# ST_LINK_V2-1.net
KiCad netlist of a schematic drawn in Altium Designer
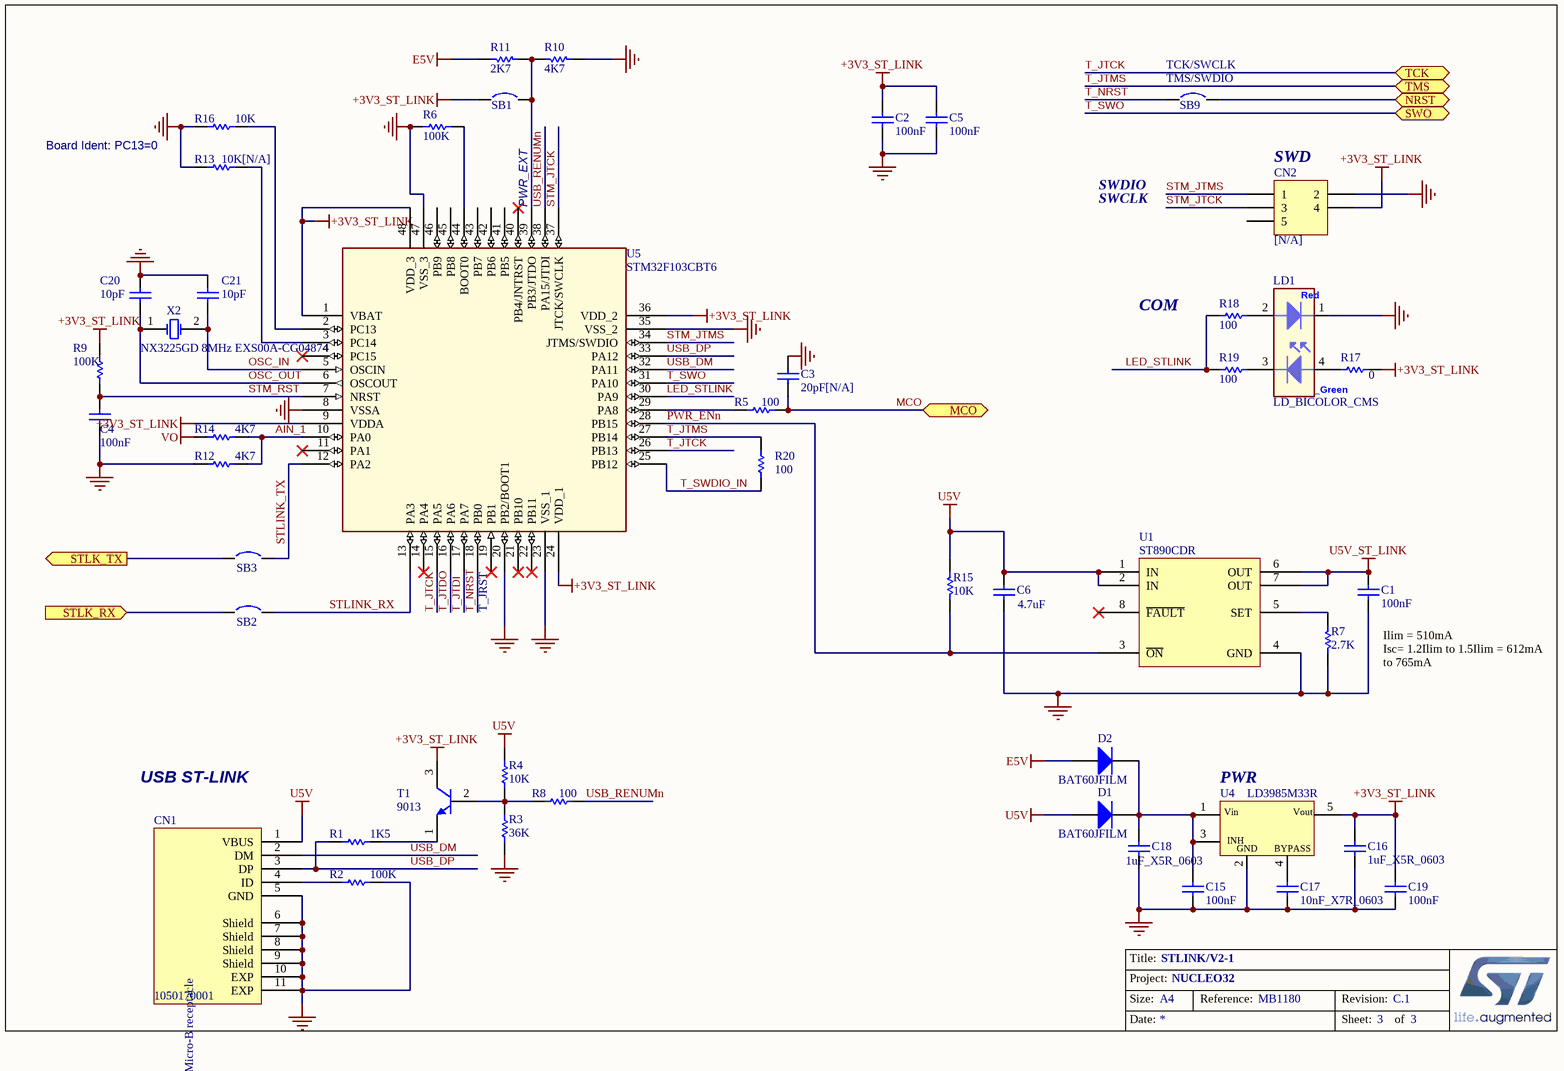
[diagram p0: ST_LINK_V2-1.SCHDOC]

(export (version "E")
  (design (tool "Eeschema 10.0.6"))
  (components
    (comp (ref "C1")
      (value "100nF")
      (footprint "0603C")
      (description "Capacitor 0402 / 0603 / 0805")
      (libsource (lib "MCD_TOOLS") (part "Capacitor_ST"))
    )
    (comp (ref "C2")
      (value "100nF")
      (footprint "0603C")
      (description "Capacitor 0402 / 0603 / 0805")
      (libsource (lib "MCD_TOOLS") (part "Capacitor_ST"))
    )
    (comp (ref "C3")
      (value "20pF[N/A]")
      (footprint "0603C")
      (description "Capacitor 0402 / 0603 / 0805")
      (libsource (lib "MCD_TOOLS") (part "Capacitor_ST"))
    )
    (comp (ref "C4")
      (value "100nF")
      (footprint "0603C")
      (description "Capacitor 0402 / 0603 / 0805")
      (libsource (lib "MCD_TOOLS") (part "Capacitor_ST"))
    )
    (comp (ref "C5")
      (value "100nF")
      (footprint "0603C")
      (description "Capacitor 0402 / 0603 / 0805")
      (libsource (lib "MCD_TOOLS") (part "Capacitor_ST"))
    )
    (comp (ref "C6")
      (value "4.7uF")
      (footprint "0603C")
      (description "0603  X5R 1µF")
      (fields (field (name "TOLERANCE") "10%"))
      (libsource (lib "MB963_1") (part "CAP SMD 0603  X5R 1µF 25V 10%"))
    )
    (comp (ref "C15")
      (value "100nF")
      (footprint "0603C")
      (description "Capacitor 0402 / 0603 / 0805")
      (libsource (lib "MCD_TOOLS") (part "Capacitor_ST"))
    )
    (comp (ref "C16")
      (value "1uF_X5R_0603")
      (footprint "0603C")
      (description "0603  X5R 1µF")
      (fields (field (name "TOLERANCE") "10%"))
      (libsource (lib "MB963_1") (part "CAP SMD 0603  X5R 1µF 25V 10%"))
    )
    (comp (ref "C17")
      (value "10nF_X7R_0603")
      (footprint "0603C")
      (description "0603  X7R 10NF")
      (fields (field (name "TOLERANCE") "10%"))
      (libsource (lib "MB963_1") (part "CAP SMD 0603  X7R 10000PF 50V 10%"))
    )
    (comp (ref "C18")
      (value "1uF_X5R_0603")
      (footprint "0603C")
      (description "0603  X5R 1µF")
      (fields (field (name "TOLERANCE") "10%"))
      (libsource (lib "MB963_1") (part "CAP SMD 0603  X5R 1µF 25V 10%"))
    )
    (comp (ref "C19")
      (value "100nF")
      (footprint "0603C")
      (description "Capacitor 0402 / 0603 / 0805")
      (libsource (lib "MCD_TOOLS") (part "Capacitor_ST"))
    )
    (comp (ref "C20")
      (value "10pF")
      (footprint "0603C")
      (description "Capacitor 0402 / 0603 / 0805")
      (libsource (lib "MCD_TOOLS") (part "Capacitor_ST"))
    )
    (comp (ref "C21")
      (value "10pF")
      (footprint "0603C")
      (description "Capacitor 0402 / 0603 / 0805")
      (libsource (lib "MCD_TOOLS") (part "Capacitor_ST"))
    )
    (comp (ref "CN1")
      (value "1050170001")
      (footprint "Molex_1050170001")
      (libsource (lib "Smartphone_accessory") (part "1050170001"))
    )
    (comp (ref "CN2")
      (value "[N/A]")
      (footprint "HDR_1x5_2R54_V_M")
      (description "Header, 3-Pin, Dual row")
      (fields (field (name "PUBLISHER") "Altium Limited"))
      (libsource (lib "Miscellaneous Connectors") (part "Header 3X2"))
    )
    (comp (ref "D1")
      (value "BAT60JFILM")
      (footprint "SOD-323")
      (libsource (lib "MCD_TOOLS") (part "BAT60JFILM"))
    )
    (comp (ref "D2")
      (value "BAT60JFILM")
      (footprint "SOD-323")
      (libsource (lib "MCD_TOOLS") (part "BAT60JFILM"))
    )
    (comp (ref "LD1")
      (value "LD_BICOLOR_CMS")
      (footprint "HSMF-A201")
      (description "Bicolor Led")
      (libsource (lib "MCD_TOOLS") (part "LD_BICOLOR_CMS"))
    )
    (comp (ref "R1")
      (value "1K5")
      (footprint "0603R")
      (description "Resistor 0402 or 0603 or 0805")
      (libsource (lib "") (part "Res1_1"))
    )
    (comp (ref "R2")
      (value "100K")
      (footprint "0603R")
      (description "Resistor 0402 or 0603 or 0805")
      (libsource (lib "") (part "Res1_1"))
    )
    (comp (ref "R3")
      (value "36K")
      (footprint "0603R")
      (description "Resistor")
      (fields (field (name "PUBLISHER") "Altium Limited"))
      (libsource (lib "Miscellaneous Devices") (part "Res1"))
    )
    (comp (ref "R4")
      (value "10K")
      (footprint "0603R")
      (description "Resistor")
      (fields (field (name "PUBLISHER") "Altium Limited"))
      (libsource (lib "Miscellaneous Devices") (part "Res1"))
    )
    (comp (ref "R5")
      (value "100")
      (footprint "0603R")
      (description "Resistor 0402 or 0603 or 0805")
      (libsource (lib "") (part "Res1_1"))
    )
    (comp (ref "R6")
      (value "100K")
      (footprint "0603R")
      (description "Resistor 0402 or 0603 or 0805")
      (libsource (lib "") (part "Res1_1"))
    )
    (comp (ref "R7")
      (value "2.7K")
      (footprint "0603R")
      (description "Resistor")
      (fields (field (name "PUBLISHER") "Altium Limited"))
      (libsource (lib "*") (part "Res1"))
    )
    (comp (ref "R8")
      (value "100")
      (footprint "0603R")
      (description "Resistor 0402 or 0603 or 0805")
      (libsource (lib "") (part "Res1_1"))
    )
    (comp (ref "R9")
      (value "100K")
      (footprint "0603R")
      (description "Resistor 0402 or 0603 or 0805")
      (libsource (lib "") (part "Res1_1"))
    )
    (comp (ref "R10")
      (value "4K7")
      (footprint "0603R")
      (description "Resistor")
      (fields (field (name "PUBLISHER") "Altium Limited"))
      (libsource (lib "") (part "Res1_2"))
    )
    (comp (ref "R11")
      (value "2K7")
      (footprint "0603R")
      (description "Resistor")
      (fields (field (name "PUBLISHER") "Altium Limited"))
      (libsource (lib "") (part "Res1_2"))
    )
    (comp (ref "R12")
      (value "4K7")
      (footprint "0603R")
      (description "Resistor 0402 or 0603 or 0805")
      (libsource (lib "") (part "Res1_1"))
    )
    (comp (ref "R13")
      (value "10K[N/A]")
      (footprint "0603R")
      (description "Resistor 0402 or 0603 or 0805")
      (libsource (lib "") (part "Res1_1"))
    )
    (comp (ref "R14")
      (value "4K7")
      (footprint "0603R")
      (description "Resistor 0402 or 0603 or 0805")
      (libsource (lib "") (part "Res1_1"))
    )
    (comp (ref "R15")
      (value "10K")
      (footprint "0603R")
      (description "Resistor")
      (fields (field (name "PUBLISHER") "Altium Limited"))
      (libsource (lib "*") (part "Res1"))
    )
    (comp (ref "R16")
      (value "10K")
      (footprint "0603R")
      (description "Resistor 0402 or 0603 or 0805")
      (libsource (lib "") (part "Res1_1"))
    )
    (comp (ref "R17")
      (value "0")
      (footprint "0603R")
      (description "Resistor 0402 or 0603 or 0805")
      (libsource (lib "") (part "Res1_1"))
    )
    (comp (ref "R18")
      (value "100")
      (footprint "0603R")
      (description "Resistor 0402 or 0603 or 0805")
      (libsource (lib "") (part "Res1_1"))
    )
    (comp (ref "R19")
      (value "100")
      (footprint "0603R")
      (description "Resistor 0402 or 0603 or 0805")
      (libsource (lib "") (part "Res1_1"))
    )
    (comp (ref "R20")
      (value "100")
      (footprint "0603R")
      (description "Resistor 0402 or 0603 or 0805")
      (libsource (lib "") (part "Res1_1"))
    )
    (comp (ref "SB1")
      (value "Circuit Breaker (open)")
      (footprint "SB_0603")
      (description "Circuit Breaker")
      (fields (field (name "PUBLISHER") "Altium Limited"))
      (libsource (lib "MB915") (part "Circuit Breaker"))
    )
    (comp (ref "SB2")
      (value "Circuit Breaker (close)")
      (footprint "SB_0603")
      (description "Circuit Breaker")
      (fields (field (name "PUBLISHER") "Altium Limited"))
      (libsource (lib "MCD_TOOLS") (part "Circuit Breaker"))
    )
    (comp (ref "SB3")
      (value "Circuit Breaker (close)")
      (footprint "SB_0603")
      (description "Circuit Breaker")
      (fields (field (name "PUBLISHER") "Altium Limited"))
      (libsource (lib "MCD_TOOLS") (part "Circuit Breaker"))
    )
    (comp (ref "SB9")
      (value "Circuit Breaker (close)")
      (footprint "SB_0603")
      (description "Circuit Breaker")
      (fields (field (name "PUBLISHER") "Altium Limited"))
      (libsource (lib "MB915") (part "Circuit Breaker"))
    )
    (comp (ref "T1")
      (value "9013")
      (footprint "SOT23-3")
      (description "NPN Bipolar Transistor")
      (fields (field (name "PUBLISHER") "Altium Limited"))
      (libsource (lib "Miscellaneous Devices") (part "NPN"))
    )
    (comp (ref "U1") (value "ST890CDR") (footprint "SO-8") (libsource (lib "MB1180") (part "ST890CDR")))
    (comp (ref "U4")
      (value "LD3985M33R")
      (footprint "SOT23-5L")
      (description "Ultra low drop-low noise BiCMOS voltage, regulators low ESR capacitors compatible")
      (libsource (lib "MCD_TOOLS") (part "LD3985M33R"))
    )
    (comp (ref "U5")
      (value "STM32F103CBT6")
      (footprint "LQFP48_0R5_7x7")
      (description "Medium-density performance line ARM-based 32-bit MCU with 64KB Flash")
      (libsource (lib "Nucleo_64") (part "STM32F103CBT6"))
    )
    (comp (ref "X2")
      (value "NX3225GD 8MHz EXS00A-CG04874")
      (footprint "XTAL_2SM_3R2x2R5")
      (description "Crystal Oscillator")
      (fields (field (name "PUBLISHER") "Altium Limited"))
      (libsource (lib "MB963_1") (part "XTAL"))
    )
  )
  (nets
    (net (code "1") (name "+3V3_ST_LINK") (class "Default")
      (node (ref "C16") (pin "1") (pinfunction "1_1") (pintype "passive"))
      (node (ref "C19") (pin "2") (pinfunction "2_2") (pintype "passive"))
      (node (ref "C2") (pin "2") (pinfunction "2_2") (pintype "passive"))
      (node (ref "C5") (pin "2") (pinfunction "2_2") (pintype "passive"))
      (node (ref "CN2") (pin "4") (pinfunction "4_4") (pintype "passive"))
      (node (ref "R17") (pin "2") (pinfunction "2_2") (pintype "passive"))
      (node (ref "R9") (pin "2") (pinfunction "2_2") (pintype "passive"))
      (node (ref "SB1") (pin "1") (pinfunction "1_1") (pintype "passive"))
      (node (ref "T1") (pin "3") (pinfunction "C_3") (pintype "passive"))
      (node (ref "U4") (pin "5") (pinfunction "Vout_5") (pintype "passive"))
      (node (ref "U5") (pin "1") (pinfunction "VBAT_1") (pintype "power_in"))
      (node (ref "U5") (pin "24") (pinfunction "VDD_1_24") (pintype "power_in"))
      (node (ref "U5") (pin "36") (pinfunction "VDD_2_36") (pintype "power_in"))
      (node (ref "U5") (pin "48") (pinfunction "VDD_3_48") (pintype "power_in"))
      (node (ref "U5") (pin "9") (pinfunction "VDDA_9") (pintype "power_in"))
    )
    (net (code "2") (name "/AIN_1") (class "Default")
      (node (ref "R12") (pin "2") (pinfunction "2_2") (pintype "passive"))
      (node (ref "R14") (pin "2") (pinfunction "2_2") (pintype "passive"))
      (node (ref "U5") (pin "10") (pinfunction "PA0_10") (pintype "bidirectional"))
    )
    (net (code "3") (name "/LED_STLINK") (class "Default")
      (node (ref "R18") (pin "1") (pinfunction "1_1") (pintype "passive"))
      (node (ref "R19") (pin "1") (pinfunction "1_1") (pintype "passive"))
      (node (ref "U5") (pin "30") (pinfunction "PA9_30") (pintype "bidirectional"))
    )
    (net (code "4") (name "/MCO") (class "Default")
      (node (ref "C3") (pin "1") (pinfunction "1_1") (pintype "passive"))
      (node (ref "R5") (pin "2") (pinfunction "2_2") (pintype "passive"))
    )
    (net (code "5") (name "/NRST") (class "Default")
      (node (ref "SB9") (pin "2") (pinfunction "2_2") (pintype "passive"))
    )
    (net (code "6") (name "/OSC_IN") (class "Default")
      (node (ref "C21") (pin "1") (pinfunction "1_1") (pintype "passive"))
      (node (ref "U5") (pin "5") (pinfunction "OSCIN_5") (pintype "input"))
      (node (ref "X2") (pin "2") (pinfunction "OSC2_2") (pintype "passive"))
    )
    (net (code "7") (name "/OSC_OUT") (class "Default")
      (node (ref "C20") (pin "1") (pinfunction "1_1") (pintype "passive"))
      (node (ref "U5") (pin "6") (pinfunction "OSCOUT_6") (pintype "output"))
      (node (ref "X2") (pin "1") (pinfunction "OSC1_1") (pintype "passive"))
    )
    (net (code "8") (name "/PWR_ENn") (class "Default")
      (node (ref "R15") (pin "2") (pinfunction "2_2") (pintype "passive"))
      (node (ref "U1") (pin "3") (pinfunction "~{ON}_3") (pintype "passive"))
      (node (ref "U5") (pin "28") (pinfunction "PB15_28") (pintype "bidirectional"))
    )
    (net (code "9") (name "/STLINK_RX") (class "Default")
      (node (ref "SB2") (pin "2") (pinfunction "2_2") (pintype "passive"))
      (node (ref "U5") (pin "13") (pinfunction "PA3_13") (pintype "bidirectional"))
    )
    (net (code "10") (name "/STLINK_TX") (class "Default")
      (node (ref "SB3") (pin "2") (pinfunction "2_2") (pintype "passive"))
      (node (ref "U5") (pin "12") (pinfunction "PA2_12") (pintype "bidirectional"))
    )
    (net (code "11") (name "/STLK_RX") (class "Default")
      (node (ref "SB2") (pin "1") (pinfunction "1_1") (pintype "passive"))
    )
    (net (code "12") (name "/STLK_TX") (class "Default")
      (node (ref "SB3") (pin "1") (pinfunction "1_1") (pintype "passive"))
    )
    (net (code "13") (name "/STM_JTCK") (class "Default")
      (node (ref "CN2") (pin "3") (pinfunction "3_3") (pintype "passive"))
      (node (ref "U5") (pin "37") (pinfunction "JTCK/SWCLK_37") (pintype "bidirectional"))
    )
    (net (code "14") (name "/STM_JTMS") (class "Default")
      (node (ref "CN2") (pin "1") (pinfunction "1_1") (pintype "passive"))
      (node (ref "U5") (pin "34") (pinfunction "JTMS/SWDIO_34") (pintype "bidirectional"))
    )
    (net (code "15") (name "/STM_RST") (class "Default")
      (node (ref "C4") (pin "2") (pinfunction "2_2") (pintype "passive"))
      (node (ref "R9") (pin "1") (pinfunction "1_1") (pintype "passive"))
      (node (ref "U5") (pin "7") (pinfunction "NRST_7") (pintype "input"))
    )
    (net (code "16") (name "/T_JTCK") (class "Default")
      (node (ref "U5") (pin "15") (pinfunction "PA5_15") (pintype "bidirectional"))
      (node (ref "U5") (pin "26") (pinfunction "PB13_26") (pintype "bidirectional"))
    )
    (net (code "17") (name "/T_JTDI") (class "Default")
      (node (ref "U5") (pin "17") (pinfunction "PA7_17") (pintype "bidirectional"))
    )
    (net (code "18") (name "/T_JTDO") (class "Default")
      (node (ref "U5") (pin "16") (pinfunction "PA6_16") (pintype "bidirectional"))
    )
    (net (code "19") (name "/T_JTMS") (class "Default")
      (node (ref "R20") (pin "2") (pinfunction "2_2") (pintype "passive"))
      (node (ref "U5") (pin "27") (pinfunction "PB14_27") (pintype "bidirectional"))
    )
    (net (code "20") (name "/T_NRST") (class "Default")
      (node (ref "SB9") (pin "1") (pinfunction "1_1") (pintype "passive"))
      (node (ref "U5") (pin "18") (pinfunction "PB0_18") (pintype "bidirectional"))
    )
    (net (code "21") (name "/T_SWDIO_IN") (class "Default")
      (node (ref "R20") (pin "1") (pinfunction "1_1") (pintype "passive"))
      (node (ref "U5") (pin "25") (pinfunction "PB12_25") (pintype "bidirectional"))
    )
    (net (code "22") (name "/T_SWO") (class "Default")
      (node (ref "U5") (pin "31") (pinfunction "PA10_31") (pintype "bidirectional"))
    )
    (net (code "23") (name "/USB_DM") (class "Default")
      (node (ref "CN1") (pin "2") (pinfunction "DM_2") (pintype "passive"))
      (node (ref "U5") (pin "32") (pinfunction "PA11_32") (pintype "bidirectional"))
    )
    (net (code "24") (name "/USB_DP") (class "Default")
      (node (ref "CN1") (pin "3") (pinfunction "DP_3") (pintype "passive"))
      (node (ref "R1") (pin "1") (pinfunction "1_1") (pintype "passive"))
      (node (ref "U5") (pin "33") (pinfunction "PA12_33") (pintype "bidirectional"))
    )
    (net (code "25") (name "/USB_RENUMn") (class "Default")
      (node (ref "R8") (pin "2") (pinfunction "2_2") (pintype "passive"))
      (node (ref "U5") (pin "38") (pinfunction "PA15/JTDI_38") (pintype "bidirectional"))
    )
    (net (code "26") (name "E5V") (class "Default")
      (node (ref "D2") (pin "1") (pinfunction "A_1") (pintype "passive"))
      (node (ref "R11") (pin "1") (pinfunction "1_1") (pintype "passive"))
    )
    (net (code "27") (name "GND") (class "Default")
      (node (ref "C1") (pin "1") (pinfunction "1_1") (pintype "passive"))
      (node (ref "C15") (pin "1") (pinfunction "1_1") (pintype "passive"))
      (node (ref "C16") (pin "2") (pinfunction "2_2") (pintype "passive"))
      (node (ref "C17") (pin "1") (pinfunction "1_1") (pintype "passive"))
      (node (ref "C18") (pin "1") (pinfunction "1_1") (pintype "passive"))
      (node (ref "C19") (pin "1") (pinfunction "1_1") (pintype "passive"))
      (node (ref "C2") (pin "1") (pinfunction "1_1") (pintype "passive"))
      (node (ref "C20") (pin "2") (pinfunction "2_2") (pintype "passive"))
      (node (ref "C21") (pin "2") (pinfunction "2_2") (pintype "passive"))
      (node (ref "C3") (pin "2") (pinfunction "2_2") (pintype "passive"))
      (node (ref "C4") (pin "1") (pinfunction "1_1") (pintype "passive"))
      (node (ref "C5") (pin "1") (pinfunction "1_1") (pintype "passive"))
      (node (ref "C6") (pin "1") (pinfunction "1_1") (pintype "passive"))
      (node (ref "CN1") (pin "10") (pinfunction "EXP_10") (pintype "passive"))
      (node (ref "CN1") (pin "11") (pinfunction "EXP_11") (pintype "passive"))
      (node (ref "CN1") (pin "5") (pinfunction "GND_5") (pintype "passive"))
      (node (ref "CN1") (pin "6") (pinfunction "Shield_6") (pintype "passive"))
      (node (ref "CN1") (pin "7") (pinfunction "Shield_7") (pintype "passive"))
      (node (ref "CN1") (pin "8") (pinfunction "Shield_8") (pintype "passive"))
      (node (ref "CN1") (pin "9") (pinfunction "Shield_9") (pintype "passive"))
      (node (ref "CN2") (pin "2") (pinfunction "2_2") (pintype "passive"))
      (node (ref "LD1") (pin "1") (pinfunction "1_1") (pintype "passive"))
      (node (ref "R10") (pin "2") (pinfunction "2_2") (pintype "passive"))
      (node (ref "R12") (pin "1") (pinfunction "1_1") (pintype "passive"))
      (node (ref "R13") (pin "1") (pinfunction "1_1") (pintype "passive"))
      (node (ref "R16") (pin "1") (pinfunction "1_1") (pintype "passive"))
      (node (ref "R2") (pin "2") (pinfunction "2_2") (pintype "passive"))
      (node (ref "R3") (pin "1") (pinfunction "1_1") (pintype "passive"))
      (node (ref "R6") (pin "1") (pinfunction "1_1") (pintype "passive"))
      (node (ref "R7") (pin "2") (pinfunction "2_2") (pintype "passive"))
      (node (ref "U1") (pin "4") (pinfunction "GND_4") (pintype "passive"))
      (node (ref "U4") (pin "2") (pinfunction "GND_2") (pintype "passive"))
      (node (ref "U5") (pin "20") (pinfunction "PB2/BOOT1_20") (pintype "bidirectional"))
      (node (ref "U5") (pin "23") (pinfunction "VSS_1_23") (pintype "power_in"))
      (node (ref "U5") (pin "35") (pinfunction "VSS_2_35") (pintype "power_in"))
      (node (ref "U5") (pin "47") (pinfunction "VSS_3_47") (pintype "power_in"))
      (node (ref "U5") (pin "8") (pinfunction "VSSA_8") (pintype "power_in"))
    )
    (net (code "28") (name "Net-(CN1-ID)") (class "Default")
      (node (ref "CN1") (pin "4") (pinfunction "ID_4") (pintype "passive"))
      (node (ref "R2") (pin "1") (pinfunction "1_1") (pintype "passive"))
    )
    (net (code "29") (name "Net-(D1-K)") (class "Default")
      (node (ref "C15") (pin "2") (pinfunction "2_2") (pintype "passive"))
      (node (ref "C18") (pin "2") (pinfunction "2_2") (pintype "passive"))
      (node (ref "D1") (pin "2") (pinfunction "K_2") (pintype "passive"))
      (node (ref "D2") (pin "2") (pinfunction "K_2") (pintype "passive"))
      (node (ref "U4") (pin "1") (pinfunction "Vin_1") (pintype "passive"))
      (node (ref "U4") (pin "3") (pinfunction "CE_3") (pintype "passive"))
    )
    (net (code "30") (name "Net-(LD1-Pad2)") (class "Default")
      (node (ref "LD1") (pin "2") (pinfunction "2_2") (pintype "passive"))
      (node (ref "R18") (pin "2") (pinfunction "2_2") (pintype "passive"))
    )
    (net (code "31") (name "Net-(LD1-Pad3)") (class "Default")
      (node (ref "LD1") (pin "3") (pinfunction "3_3") (pintype "passive"))
      (node (ref "R19") (pin "2") (pinfunction "2_2") (pintype "passive"))
    )
    (net (code "32") (name "Net-(LD1-Pad4)") (class "Default")
      (node (ref "LD1") (pin "4") (pinfunction "4_4") (pintype "passive"))
      (node (ref "R17") (pin "1") (pinfunction "1_1") (pintype "passive"))
    )
    (net (code "33") (name "Net-(T1-B)") (class "Default")
      (node (ref "R3") (pin "2") (pinfunction "2_2") (pintype "passive"))
      (node (ref "R4") (pin "1") (pinfunction "1_1") (pintype "passive"))
      (node (ref "R8") (pin "1") (pinfunction "1_1") (pintype "passive"))
      (node (ref "T1") (pin "2") (pinfunction "B_2") (pintype "passive"))
    )
    (net (code "34") (name "Net-(T1-E)") (class "Default")
      (node (ref "R1") (pin "2") (pinfunction "2_2") (pintype "passive"))
      (node (ref "T1") (pin "1") (pinfunction "E_1") (pintype "passive"))
    )
    (net (code "35") (name "Net-(U1-SET)") (class "Default")
      (node (ref "R7") (pin "1") (pinfunction "1_1") (pintype "passive"))
      (node (ref "U1") (pin "5") (pinfunction "SET_5") (pintype "passive"))
    )
    (net (code "36") (name "Net-(U4-BYPASS)") (class "Default")
      (node (ref "C17") (pin "2") (pinfunction "2_2") (pintype "passive"))
      (node (ref "U4") (pin "4") (pinfunction "BYPASS_4") (pintype "passive"))
    )
    (net (code "37") (name "Net-(U5-BOOT0)") (class "Default")
      (node (ref "R6") (pin "2") (pinfunction "2_2") (pintype "passive"))
      (node (ref "U5") (pin "44") (pinfunction "BOOT0_44") (pintype "bidirectional"))
    )
    (net (code "38") (name "Net-(U5-PA8)") (class "Default")
      (node (ref "R5") (pin "1") (pinfunction "1_1") (pintype "passive"))
      (node (ref "U5") (pin "29") (pinfunction "PA8_29") (pintype "bidirectional"))
    )
    (net (code "39") (name "Net-(U5-PB3{slash}JTDO)") (class "Default")
      (node (ref "R10") (pin "1") (pinfunction "1_1") (pintype "passive"))
      (node (ref "R11") (pin "2") (pinfunction "2_2") (pintype "passive"))
      (node (ref "SB1") (pin "2") (pinfunction "2_2") (pintype "passive"))
      (node (ref "U5") (pin "39") (pinfunction "PB3/JTDO_39") (pintype "bidirectional"))
    )
    (net (code "40") (name "Net-(U5-PC13)") (class "Default")
      (node (ref "R16") (pin "2") (pinfunction "2_2") (pintype "passive"))
      (node (ref "U5") (pin "2") (pinfunction "PC13_2") (pintype "bidirectional"))
    )
    (net (code "41") (name "Net-(U5-PC14)") (class "Default")
      (node (ref "R13") (pin "2") (pinfunction "2_2") (pintype "passive"))
      (node (ref "U5") (pin "3") (pinfunction "PC14_3") (pintype "bidirectional"))
    )
    (net (code "42") (name "U5V") (class "Default")
      (node (ref "C6") (pin "2") (pinfunction "2_2") (pintype "passive"))
      (node (ref "CN1") (pin "1") (pinfunction "VBUS_1") (pintype "passive"))
      (node (ref "D1") (pin "1") (pinfunction "A_1") (pintype "passive"))
      (node (ref "R15") (pin "1") (pinfunction "1_1") (pintype "passive"))
      (node (ref "R4") (pin "2") (pinfunction "2_2") (pintype "passive"))
      (node (ref "U1") (pin "1") (pinfunction "IN_1") (pintype "passive"))
      (node (ref "U1") (pin "2") (pinfunction "IN_2") (pintype "passive"))
    )
    (net (code "43") (name "U5V_ST_LINK") (class "Default")
      (node (ref "C1") (pin "2") (pinfunction "2_2") (pintype "passive"))
      (node (ref "U1") (pin "6") (pinfunction "OUT_6") (pintype "passive"))
      (node (ref "U1") (pin "7") (pinfunction "OUT_7") (pintype "passive"))
    )
    (net (code "44") (name "VO") (class "Default")
      (node (ref "R14") (pin "1") (pinfunction "1_1") (pintype "passive"))
    )
    (net (code "45") (name "unconnected-(CN2-Pad5)") (class "Default")
      (node (ref "CN2") (pin "5") (pinfunction "5_5") (pintype "passive"))
    )
    (net (code "46") (name "unconnected-(U1-~{FAULT}-Pad8)") (class "Default")
      (node (ref "U1") (pin "8") (pinfunction "~{FAULT}_8") (pintype "passive+no_connect"))
    )
    (net (code "47") (name "unconnected-(U5-PA1-Pad11)") (class "Default")
      (node (ref "U5") (pin "11") (pinfunction "PA1_11") (pintype "bidirectional+no_connect"))
    )
    (net (code "48") (name "unconnected-(U5-PA4-Pad14)") (class "Default")
      (node (ref "U5") (pin "14") (pinfunction "PA4_14") (pintype "bidirectional+no_connect"))
    )
    (net (code "49") (name "unconnected-(U5-PB1-Pad19)") (class "Default")
      (node (ref "U5") (pin "19") (pinfunction "PB1_19") (pintype "input+no_connect"))
    )
    (net (code "50") (name "unconnected-(U5-PB4{slash}JNTRST-Pad40)") (class "Default")
      (node (ref "U5") (pin "40") (pinfunction "PB4/JNTRST_40") (pintype "bidirectional+no_connect"))
    )
    (net (code "51") (name "unconnected-(U5-PB5-Pad41)") (class "Default")
      (node (ref "U5") (pin "41") (pinfunction "PB5_41") (pintype "bidirectional"))
    )
    (net (code "52") (name "unconnected-(U5-PB6-Pad42)") (class "Default")
      (node (ref "U5") (pin "42") (pinfunction "PB6_42") (pintype "bidirectional"))
    )
    (net (code "53") (name "unconnected-(U5-PB7-Pad43)") (class "Default")
      (node (ref "U5") (pin "43") (pinfunction "PB7_43") (pintype "bidirectional"))
    )
    (net (code "54") (name "unconnected-(U5-PB8-Pad45)") (class "Default")
      (node (ref "U5") (pin "45") (pinfunction "PB8_45") (pintype "bidirectional"))
    )
    (net (code "55") (name "unconnected-(U5-PB9-Pad46)") (class "Default")
      (node (ref "U5") (pin "46") (pinfunction "PB9_46") (pintype "bidirectional"))
    )
    (net (code "56") (name "unconnected-(U5-PB10-Pad21)") (class "Default")
      (node (ref "U5") (pin "21") (pinfunction "PB10_21") (pintype "bidirectional+no_connect"))
    )
    (net (code "57") (name "unconnected-(U5-PB11-Pad22)") (class "Default")
      (node (ref "U5") (pin "22") (pinfunction "PB11_22") (pintype "bidirectional+no_connect"))
    )
    (net (code "58") (name "unconnected-(U5-PC15-Pad4)") (class "Default")
      (node (ref "U5") (pin "4") (pinfunction "PC15_4") (pintype "bidirectional+no_connect"))
    )
  )
)
